# esptoy_v200.net
KiCad netlist of a schematic drawn in EAGLE
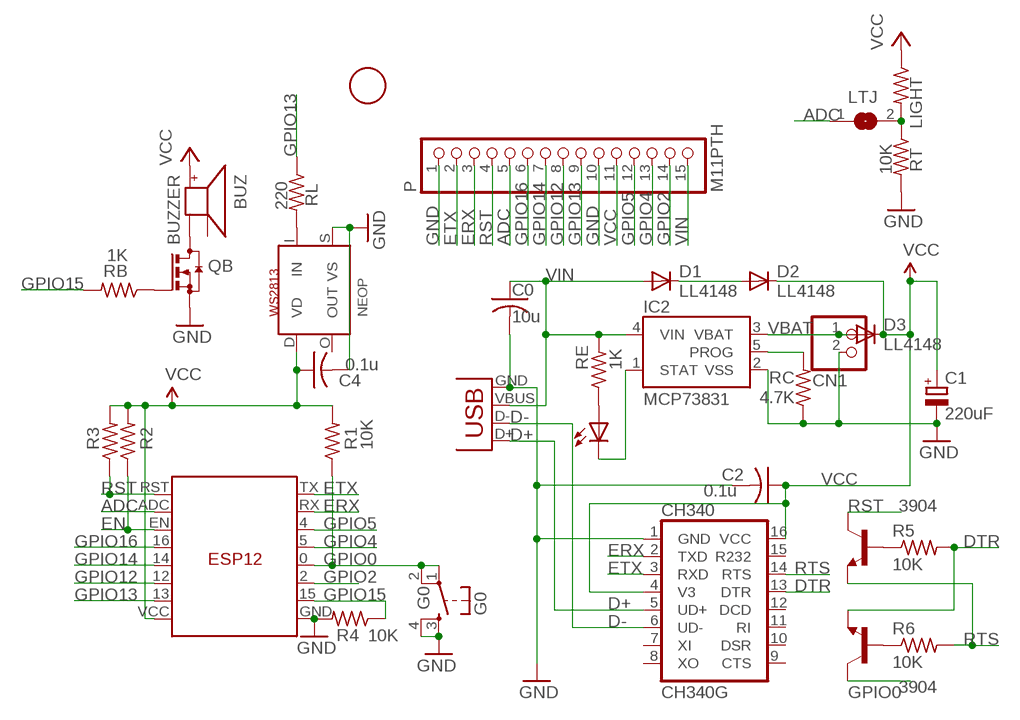
[diagram p0: schematic, sheet 1]

(export (version "E")
  (design (tool "Eeschema 10.0.6"))
  (components
    (comp (ref "1F")
      (value "FIDUCIAL")
      (footprint "eagle-import:FIDUCIAL_1MM")
      (libsource (lib "eagle-import") (part "FIDUCIAL"))
    )
    (comp (ref "BUZ")
      (value "BUZZER")
      (footprint "eagle-import:SMT-8585-BUZZER")
      (libsource (lib "eagle-import") (part "BUZZER"))
    )
    (comp (ref "C0")
      (value "10u")
      (footprint "eagle-import:C0805K")
      (libsource (lib "eagle-import") (part "adafruit2013_C-USC0805K"))
    )
    (comp (ref "C1")
      (value "220uF")
      (footprint "eagle-import:CT3528")
      (libsource (lib "eagle-import") (part "CPOL-EUCT3528"))
    )
    (comp (ref "C2")
      (value "0.1u")
      (footprint "eagle-import:C0603K")
      (libsource (lib "eagle-import") (part "C-USC0603K"))
    )
    (comp (ref "C4")
      (value "0.1u")
      (footprint "eagle-import:C0603K")
      (libsource (lib "eagle-import") (part "C-USC0603K"))
    )
    (comp (ref "CH340")
      (value "CH340G")
      (footprint "eagle-import:SO16")
      (libsource (lib "eagle-import") (part "CH340G"))
    )
    (comp (ref "CHG")
      (value "0805")
      (footprint "eagle-import:CHIPLED_0805")
      (libsource (lib "eagle-import") (part "LEDCHIPLED_0805"))
    )
    (comp (ref "CN1")
      (value "JST_2PIN-SMT-RA")
      (footprint "eagle-import:JST-PH-2-SMT-RA")
      (libsource (lib "eagle-import") (part "JST_2PIN-SMT-RA"))
    )
    (comp (ref "D1")
      (value "LL4148")
      (footprint "eagle-import:DO-214AC")
      (libsource (lib "eagle-import") (part "DIODE-DO-214AC"))
    )
    (comp (ref "D2")
      (value "LL4148")
      (footprint "eagle-import:DO-214AC")
      (libsource (lib "eagle-import") (part "DIODE-DO-214AC"))
    )
    (comp (ref "D3")
      (value "LL4148")
      (footprint "eagle-import:DO-214AC")
      (libsource (lib "eagle-import") (part "DIODE-DO-214AC"))
    )
    (comp (ref "G0")
      (value "G0")
      (footprint "eagle-import:TACTILE_SWITCH_SMD")
      (libsource (lib "eagle-import") (part "TAC_SWITCHSMD"))
    )
    (comp (ref "IC2")
      (value "MCP73831")
      (footprint "eagle-import:SOT23-5")
      (libsource (lib "eagle-import") (part "MCP73831"))
    )
    (comp (ref "LIGHT")
      (value "100K")
      (footprint "eagle-import:R1206")
      (libsource (lib "eagle-import") (part "adafruit2013_R-US_R1206"))
    )
    (comp (ref "LTJ") (value "SJ") (footprint "eagle-import:SJ") (libsource (lib "eagle-import") (part "SJ")))
    (comp (ref "NEOP")
      (value "WS2813")
      (footprint "eagle-import:RGBLED5050_4")
      (libsource (lib "eagle-import") (part "WS2813"))
    )
    (comp (ref "P")
      (value "M11PTH")
      (footprint "eagle-import:1X15-CB")
      (libsource (lib "eagle-import") (part "PINHD-1X15-CB"))
    )
    (comp (ref "QB")
      (value "AO3400")
      (footprint "eagle-import:SOT23")
      (libsource (lib "eagle-import") (part "BSS123"))
    )
    (comp (ref "R1")
      (value "10K")
      (footprint "eagle-import:R0603")
      (libsource (lib "eagle-import") (part "R-US_R0603"))
    )
    (comp (ref "R2")
      (value "10K")
      (footprint "eagle-import:R0603")
      (libsource (lib "eagle-import") (part "R-US_R0603"))
    )
    (comp (ref "R3")
      (value "10K")
      (footprint "eagle-import:R0603")
      (libsource (lib "eagle-import") (part "R-US_R0603"))
    )
    (comp (ref "R4")
      (value "10K")
      (footprint "eagle-import:R0603")
      (libsource (lib "eagle-import") (part "R-US_R0603"))
    )
    (comp (ref "R5")
      (value "10K")
      (footprint "eagle-import:R0603")
      (libsource (lib "eagle-import") (part "adafruit2013_R-US_R0603"))
    )
    (comp (ref "R6")
      (value "10K")
      (footprint "eagle-import:R0603")
      (libsource (lib "eagle-import") (part "adafruit2013_R-US_R0603"))
    )
    (comp (ref "RB")
      (value "1K")
      (footprint "eagle-import:R0603")
      (libsource (lib "eagle-import") (part "R-US_R0603"))
    )
    (comp (ref "RC")
      (value "4.7K")
      (footprint "eagle-import:R0603")
      (libsource (lib "eagle-import") (part "adafruit2013_R-US_R0603"))
    )
    (comp (ref "RE")
      (value "1K")
      (footprint "eagle-import:R0603")
      (libsource (lib "eagle-import") (part "R-US_R0603"))
    )
    (comp (ref "RL")
      (value "220")
      (footprint "eagle-import:R0603")
      (libsource (lib "eagle-import") (part "adafruit2013_R-US_R0603"))
    )
    (comp (ref "RT")
      (value "10K")
      (footprint "eagle-import:R0603")
      (libsource (lib "eagle-import") (part "adafruit2013_R-US_R0603"))
    )
    (comp (ref "T1")
      (value "3904")
      (footprint "eagle-import:SOT23-BEC")
      (libsource (lib "eagle-import") (part "-NPN-SOT23-BECMMBT3904LT1"))
    )
    (comp (ref "T2")
      (value "3904")
      (footprint "eagle-import:SOT23-BEC")
      (libsource (lib "eagle-import") (part "-NPN-SOT23-BECMMBT3904LT1"))
    )
    (comp (ref "U$1")
      (value "ESP8266")
      (footprint "eagle-import:ESP12")
      (libsource (lib "eagle-import") (part "ESP12"))
    )
    (comp (ref "X3")
      (value "USBMICROB2")
      (footprint "eagle-import:USB-MICROB2")
      (libsource (lib "eagle-import") (part "USBMICROB2"))
    )
  )
  (nets
    (net (code "1") (name "/ADC") (class "Default")
      (node (ref "LTJ") (pin "1") (pinfunction "1_1") (pintype "passive"))
      (node (ref "P") (pin "5") (pinfunction "5_5") (pintype "passive"))
      (node (ref "U$1") (pin "ADC") (pinfunction "ADC_ADC") (pintype "bidirectional"))
    )
    (net (code "2") (name "/D+") (class "Default")
      (node (ref "CH340") (pin "5") (pinfunction "UD+_5") (pintype "bidirectional"))
      (node (ref "X3") (pin "D+") (pinfunction "D+_D+") (pintype "bidirectional"))
    )
    (net (code "3") (name "/D-") (class "Default")
      (node (ref "CH340") (pin "6") (pinfunction "UD-_6") (pintype "bidirectional"))
      (node (ref "X3") (pin "D-") (pinfunction "D-_D-") (pintype "bidirectional"))
    )
    (net (code "4") (name "/DTR") (class "Default")
      (node (ref "CH340") (pin "13") (pinfunction "DTR_13") (pintype "bidirectional"))
      (node (ref "R5") (pin "2") (pinfunction "2_2") (pintype "passive"))
      (node (ref "T2") (pin "E") (pinfunction "E_E") (pintype "passive"))
    )
    (net (code "5") (name "/EN") (class "Default")
      (node (ref "R2") (pin "1") (pinfunction "1_1") (pintype "passive"))
      (node (ref "U$1") (pin "EN") (pinfunction "EN_EN") (pintype "bidirectional"))
    )
    (net (code "6") (name "/ERX") (class "Default")
      (node (ref "CH340") (pin "2") (pinfunction "TXD_2") (pintype "bidirectional"))
      (node (ref "P") (pin "3") (pinfunction "3_3") (pintype "passive"))
      (node (ref "U$1") (pin "RX") (pinfunction "RX_RX") (pintype "bidirectional"))
    )
    (net (code "7") (name "/ETX") (class "Default")
      (node (ref "CH340") (pin "3") (pinfunction "RXD_3") (pintype "bidirectional"))
      (node (ref "P") (pin "2") (pinfunction "2_2") (pintype "passive"))
      (node (ref "U$1") (pin "TX") (pinfunction "TX_TX") (pintype "bidirectional"))
    )
    (net (code "8") (name "/GPIO0") (class "Default")
      (node (ref "G0") (pin "1") (pinfunction "1_1") (pintype "passive"))
      (node (ref "G0") (pin "2") (pinfunction "2_2") (pintype "passive"))
      (node (ref "R1") (pin "1") (pinfunction "1_1") (pintype "passive"))
      (node (ref "T2") (pin "C") (pinfunction "C_C") (pintype "passive"))
      (node (ref "U$1") (pin "0") (pinfunction "G0_0") (pintype "bidirectional"))
    )
    (net (code "9") (name "/GPIO2") (class "Default")
      (node (ref "P") (pin "14") (pinfunction "14_14") (pintype "passive"))
      (node (ref "U$1") (pin "2") (pinfunction "G2_2") (pintype "bidirectional"))
    )
    (net (code "10") (name "/GPIO4") (class "Default")
      (node (ref "P") (pin "13") (pinfunction "13_13") (pintype "passive"))
      (node (ref "U$1") (pin "5") (pinfunction "G5_5") (pintype "bidirectional"))
    )
    (net (code "11") (name "/GPIO5") (class "Default")
      (node (ref "P") (pin "12") (pinfunction "12_12") (pintype "passive"))
      (node (ref "U$1") (pin "4") (pinfunction "G4_4") (pintype "bidirectional"))
    )
    (net (code "12") (name "/GPIO12") (class "Default")
      (node (ref "P") (pin "8") (pinfunction "8_8") (pintype "passive"))
      (node (ref "U$1") (pin "12") (pinfunction "G12_12") (pintype "bidirectional"))
    )
    (net (code "13") (name "/GPIO13") (class "Default")
      (node (ref "P") (pin "9") (pinfunction "9_9") (pintype "passive"))
      (node (ref "RL") (pin "1") (pinfunction "1_1") (pintype "passive"))
      (node (ref "U$1") (pin "13") (pinfunction "G13_13") (pintype "bidirectional"))
    )
    (net (code "14") (name "/GPIO14") (class "Default")
      (node (ref "P") (pin "7") (pinfunction "7_7") (pintype "passive"))
      (node (ref "U$1") (pin "14") (pinfunction "G14_14") (pintype "bidirectional"))
    )
    (net (code "15") (name "/GPIO15") (class "Default")
      (node (ref "R4") (pin "1") (pinfunction "1_1") (pintype "passive"))
      (node (ref "RB") (pin "2") (pinfunction "2_2") (pintype "passive"))
      (node (ref "U$1") (pin "15") (pinfunction "G15_15") (pintype "bidirectional"))
    )
    (net (code "16") (name "/GPIO16") (class "Default")
      (node (ref "P") (pin "6") (pinfunction "6_6") (pintype "passive"))
      (node (ref "U$1") (pin "16") (pinfunction "G16_16") (pintype "bidirectional"))
    )
    (net (code "17") (name "/RST") (class "Default")
      (node (ref "P") (pin "4") (pinfunction "4_4") (pintype "passive"))
      (node (ref "R3") (pin "1") (pinfunction "1_1") (pintype "passive"))
      (node (ref "T1") (pin "C") (pinfunction "C_C") (pintype "passive"))
      (node (ref "U$1") (pin "RST") (pinfunction "RST_RST") (pintype "bidirectional"))
    )
    (net (code "18") (name "/RTS") (class "Default")
      (node (ref "CH340") (pin "14") (pinfunction "RTS_14") (pintype "bidirectional"))
      (node (ref "R6") (pin "2") (pinfunction "2_2") (pintype "passive"))
      (node (ref "T1") (pin "E") (pinfunction "E_E") (pintype "passive"))
    )
    (net (code "19") (name "/VBAT") (class "Default")
      (node (ref "CN1") (pin "1") (pinfunction "2_1") (pintype "passive"))
      (node (ref "D3") (pin "A") (pinfunction "A_A") (pintype "passive"))
      (node (ref "IC2") (pin "3") (pinfunction "VBAT_3") (pintype "power_in"))
    )
    (net (code "20") (name "/VIN") (class "Default")
      (node (ref "C0") (pin "1") (pinfunction "1_1") (pintype "passive"))
      (node (ref "D1") (pin "A") (pinfunction "A_A") (pintype "passive"))
      (node (ref "IC2") (pin "4") (pinfunction "VIN_4") (pintype "power_in"))
      (node (ref "P") (pin "15") (pinfunction "15_15") (pintype "passive"))
      (node (ref "RE") (pin "2") (pinfunction "2_2") (pintype "passive"))
      (node (ref "X3") (pin "VBUS") (pinfunction "VBUS_VBUS") (pintype "bidirectional"))
    )
    (net (code "21") (name "GND") (class "Default")
      (node (ref "C0") (pin "2") (pinfunction "2_2") (pintype "passive"))
      (node (ref "C1") (pin "-") (pinfunction "-_-") (pintype "passive"))
      (node (ref "C2") (pin "2") (pinfunction "2_2") (pintype "passive"))
      (node (ref "C4") (pin "2") (pinfunction "2_2") (pintype "passive"))
      (node (ref "CH340") (pin "1") (pinfunction "GND_1") (pintype "power_in"))
      (node (ref "CN1") (pin "2") (pinfunction "1_2") (pintype "passive"))
      (node (ref "G0") (pin "3") (pinfunction "3_3") (pintype "passive"))
      (node (ref "G0") (pin "4") (pinfunction "4_4") (pintype "passive"))
      (node (ref "IC2") (pin "2") (pinfunction "VSS_2") (pintype "power_in"))
      (node (ref "NEOP") (pin "S") (pinfunction "VS_S") (pintype "power_in"))
      (node (ref "P") (pin "1") (pinfunction "1_1") (pintype "passive"))
      (node (ref "P") (pin "10") (pinfunction "10_10") (pintype "passive"))
      (node (ref "QB") (pin "2") (pinfunction "S_2") (pintype "passive"))
      (node (ref "R4") (pin "2") (pinfunction "2_2") (pintype "passive"))
      (node (ref "RC") (pin "1") (pinfunction "1_1") (pintype "passive"))
      (node (ref "RT") (pin "2") (pinfunction "2_2") (pintype "passive"))
      (node (ref "U$1") (pin "GND") (pinfunction "GND_GND") (pintype "power_in"))
      (node (ref "X3") (pin "GND") (pinfunction "GND_GND") (pintype "bidirectional"))
    )
    (net (code "22") (name "Net-(CHG-PadA)") (class "Default")
      (node (ref "CHG") (pin "A") (pinfunction "A_A") (pintype "passive"))
      (node (ref "RE") (pin "1") (pinfunction "1_1") (pintype "passive"))
    )
    (net (code "23") (name "Net-(D1-PadC)") (class "Default")
      (node (ref "D1") (pin "C") (pinfunction "C_C") (pintype "passive"))
      (node (ref "D2") (pin "A") (pinfunction "A_A") (pintype "passive"))
    )
    (net (code "24") (name "Net-(IC2-PROG)") (class "Default")
      (node (ref "IC2") (pin "5") (pinfunction "PROG_5") (pintype "input"))
      (node (ref "RC") (pin "2") (pinfunction "2_2") (pintype "passive"))
    )
    (net (code "25") (name "Net-(IC2-STAT)") (class "Default")
      (node (ref "CHG") (pin "C") (pinfunction "C_C") (pintype "passive"))
      (node (ref "IC2") (pin "1") (pinfunction "STAT_1") (pintype "output"))
    )
    (net (code "26") (name "Net-(LIGHT-Pad2)") (class "Default")
      (node (ref "LIGHT") (pin "2") (pinfunction "2_2") (pintype "passive"))
      (node (ref "LTJ") (pin "2") (pinfunction "2_2") (pintype "passive"))
      (node (ref "RT") (pin "1") (pinfunction "1_1") (pintype "passive"))
    )
    (net (code "27") (name "Net-(NEOP-IN)") (class "Default")
      (node (ref "NEOP") (pin "I") (pinfunction "IN_I") (pintype "input"))
      (node (ref "RL") (pin "2") (pinfunction "2_2") (pintype "passive"))
    )
    (net (code "28") (name "Net-(QB-D)") (class "Default")
      (node (ref "BUZ") (pin "-") (pinfunction "-_-") (pintype "passive"))
      (node (ref "QB") (pin "3") (pinfunction "D_3") (pintype "passive"))
    )
    (net (code "29") (name "Net-(QB-G)") (class "Default")
      (node (ref "QB") (pin "1") (pinfunction "G_1") (pintype "passive"))
      (node (ref "RB") (pin "1") (pinfunction "1_1") (pintype "passive"))
    )
    (net (code "30") (name "Net-(R5-Pad1)") (class "Default")
      (node (ref "R5") (pin "1") (pinfunction "1_1") (pintype "passive"))
      (node (ref "T1") (pin "B") (pinfunction "B_B") (pintype "passive"))
    )
    (net (code "31") (name "Net-(R6-Pad1)") (class "Default")
      (node (ref "R6") (pin "1") (pinfunction "1_1") (pintype "passive"))
      (node (ref "T2") (pin "B") (pinfunction "B_B") (pintype "passive"))
    )
    (net (code "32") (name "VCC") (class "Default")
      (node (ref "BUZ") (pin "+") (pinfunction "+_+") (pintype "passive"))
      (node (ref "C1") (pin "+") (pinfunction "+_+") (pintype "passive"))
      (node (ref "C2") (pin "1") (pinfunction "1_1") (pintype "passive"))
      (node (ref "C4") (pin "1") (pinfunction "1_1") (pintype "passive"))
      (node (ref "CH340") (pin "16") (pinfunction "VCC_16") (pintype "power_in"))
      (node (ref "CH340") (pin "4") (pinfunction "V3_4") (pintype "bidirectional"))
      (node (ref "D2") (pin "C") (pinfunction "C_C") (pintype "passive"))
      (node (ref "D3") (pin "C") (pinfunction "C_C") (pintype "passive"))
      (node (ref "LIGHT") (pin "1") (pinfunction "1_1") (pintype "passive"))
      (node (ref "NEOP") (pin "D") (pinfunction "VD_D") (pintype "power_in"))
      (node (ref "P") (pin "11") (pinfunction "11_11") (pintype "passive"))
      (node (ref "R1") (pin "2") (pinfunction "2_2") (pintype "passive"))
      (node (ref "R2") (pin "2") (pinfunction "2_2") (pintype "passive"))
      (node (ref "R3") (pin "2") (pinfunction "2_2") (pintype "passive"))
      (node (ref "U$1") (pin "VCC") (pinfunction "VCC_VCC") (pintype "power_in"))
    )
    (net (code "33") (name "unconnected-(BUZ-PadA-)") (class "Default")
      (node (ref "BUZ") (pin "A-") (pinfunction "A-_A-") (pintype "passive"))
    )
    (net (code "34") (name "unconnected-(CH340-CTS-Pad9)") (class "Default")
      (node (ref "CH340") (pin "9") (pinfunction "CTS_9") (pintype "bidirectional"))
    )
    (net (code "35") (name "unconnected-(CH340-DCD-Pad12)") (class "Default")
      (node (ref "CH340") (pin "12") (pinfunction "DCD_12") (pintype "bidirectional"))
    )
    (net (code "36") (name "unconnected-(CH340-DSR-Pad10)") (class "Default")
      (node (ref "CH340") (pin "10") (pinfunction "DSR_10") (pintype "bidirectional"))
    )
    (net (code "37") (name "unconnected-(CH340-R232-Pad15)") (class "Default")
      (node (ref "CH340") (pin "15") (pinfunction "R232_15") (pintype "bidirectional"))
    )
    (net (code "38") (name "unconnected-(CH340-RI-Pad11)") (class "Default")
      (node (ref "CH340") (pin "11") (pinfunction "RI_11") (pintype "bidirectional"))
    )
    (net (code "39") (name "unconnected-(CH340-XI-Pad7)") (class "Default")
      (node (ref "CH340") (pin "7") (pinfunction "XI_7") (pintype "bidirectional"))
    )
    (net (code "40") (name "unconnected-(CH340-XO-Pad8)") (class "Default")
      (node (ref "CH340") (pin "8") (pinfunction "XO_8") (pintype "bidirectional"))
    )
    (net (code "41") (name "unconnected-(NEOP-OUT-PadO)") (class "Default")
      (node (ref "NEOP") (pin "O") (pinfunction "OUT_O") (pintype "output"))
    )
  )
)
